# Power.net
KiCad netlist of a schematic drawn in Altium Designer
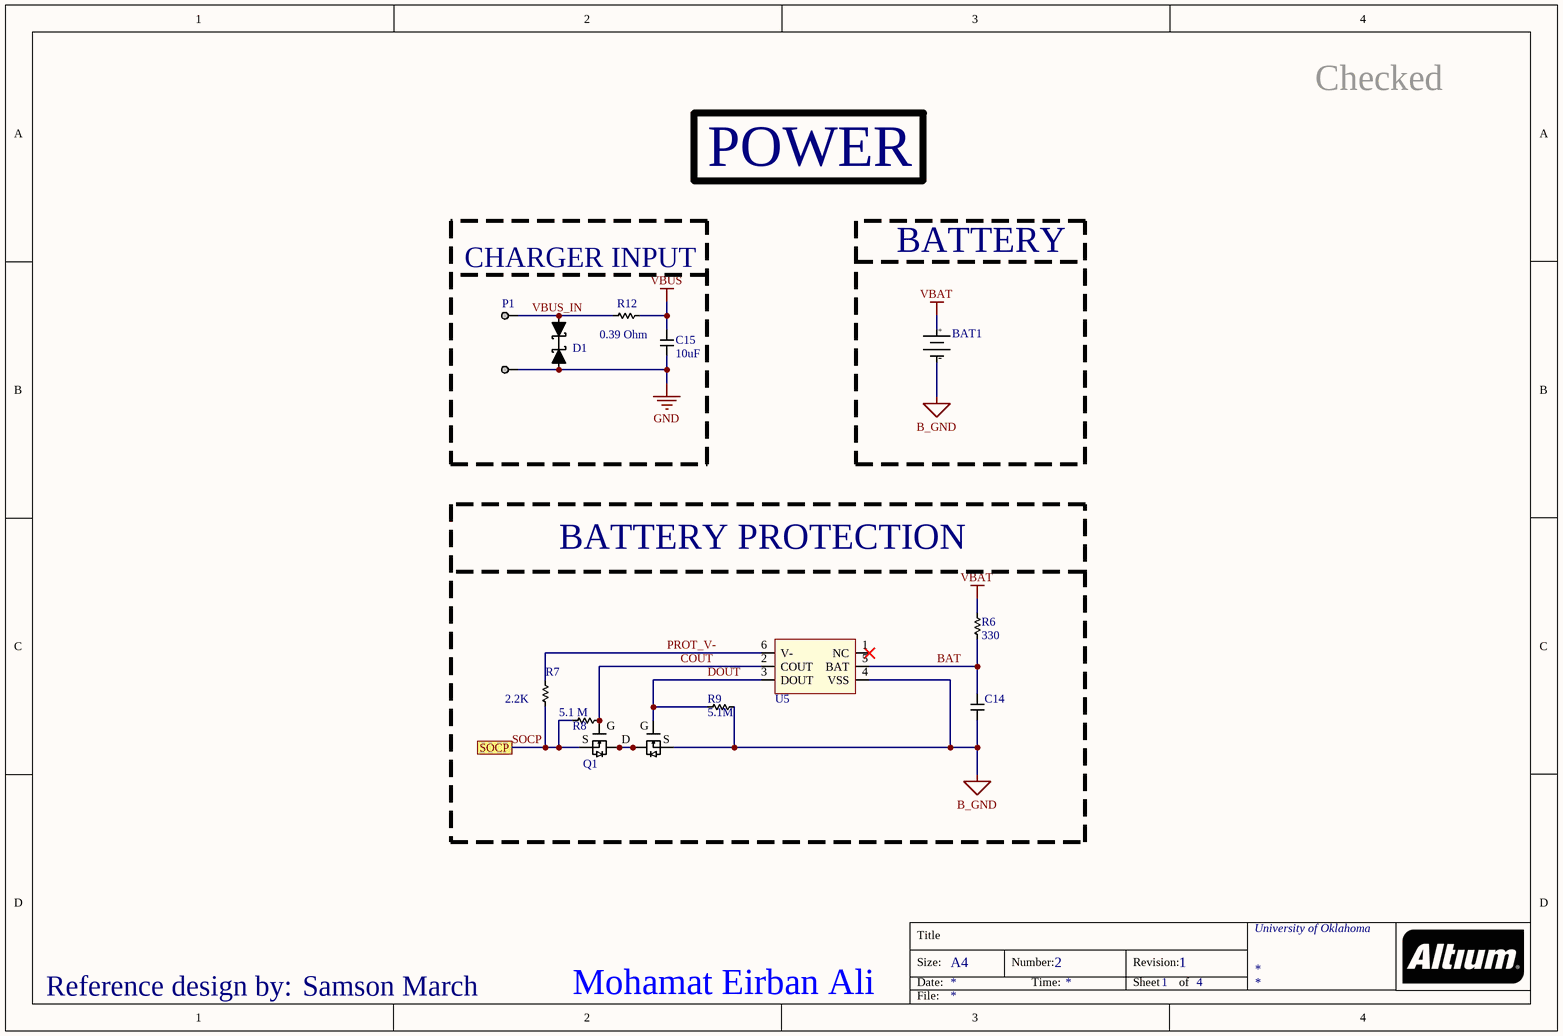
[diagram p0: Power.SchDoc]

(export (version "E")
  (design (tool "Eeschema 10.0.6"))
  (components
    (comp (ref "BAT1")
      (value "~")
      (footprint "RJD2430C1ST1")
      (description "Coin, 24.5mm 3.7V Lithium-Ion Battery Rechargeable (Secondary) 110mAh")
      (libsource (lib "smarchWatch_V5") (part "RJD2430C1ST1"))
    )
    (comp (ref "C14")
      (value "~")
      (footprint "CAP_0603_HIGH")
      (description "0603 Capacitor")
      (fields (field (name "TOLERANCE") "10%") (field (name "VOLTAGE") "50V"))
      (libsource (lib "smarchWatch_V5") (part "Capacitor_0603"))
    )
    (comp (ref "C15")
      (value "10uF")
      (footprint "CAP_0603_HIGH")
      (description "0603 Capacitor")
      (libsource (lib "smarchWatch_V5") (part "Capacitor_0603_1"))
    )
    (comp (ref "D1")
      (value "~")
      (footprint "ESD9B5.0ST5G")
      (description "TVS DIODE 5V SOD923")
      (libsource (lib "smarchWatch_V5") (part "ESD9B5.0ST5G"))
    )
    (comp (ref "P1")
      (value "~")
      (footprint "800-10-002-30-507101")
      (description "2 Position Spring Mating Target Connector Surface Mount")
      (libsource (lib "smarchWatch_V5") (part "800-10-002-30-507101"))
    )
    (comp (ref "Q1")
      (value "~")
      (footprint "ECH8693R-TL-W")
      (description "Mosfet Array 2 N-Channel (Dual) Common Drain 24V 14A 1.4W Surface Mount SOT-28FL/ECH8")
      (libsource (lib "smarchWatch_V5") (part "ECH8693R-TL-W"))
    )
    (comp (ref "R6")
      (value "330")
      (footprint "RES_0603_HIGH")
      (description "0603 Resistor")
      (libsource (lib "smarchWatch_V5") (part "Resistor_0603_2"))
    )
    (comp (ref "R7")
      (value "2.2K")
      (footprint "RES_0603_HIGH")
      (description "0603 Resistor")
      (libsource (lib "smarchWatch_V5") (part "Resistor_0603_1"))
    )
    (comp (ref "R8")
      (value "5.1 M")
      (footprint "RES_0603_HIGH")
      (description "0603 Resistor")
      (fields (field (name "TOLERANCE") "5%"))
      (libsource (lib "smarchWatch_V5") (part "Resistor_0603"))
    )
    (comp (ref "R9")
      (value "5.1M")
      (footprint "RES_0603_HIGH")
      (description "0603 Resistor")
      (fields (field (name "TOLERANCE") "5%"))
      (libsource (lib "smLib") (part "Resistor_0603"))
    )
    (comp (ref "R12")
      (value "0.39 Ohm")
      (footprint "RES_0805_HIGH")
      (description "0805 Resistor")
      (libsource (lib "smarchWatch_V5") (part "Resistor_0805"))
    )
    (comp (ref "U5")
      (value "~")
      (footprint "BQ29700DSER")
      (description "Battery Battery Protection IC Lithium-Ion/Polymer 6-WSON (1.5x1.5)")
      (libsource (lib "smarchWatch_V5") (part "BQ29700DSER"))
    )
  )
  (nets
    (net (code "1") (name "/BAT") (class "Default")
      (node (ref "C14") (pin "1") (pinfunction "1_1") (pintype "passive"))
      (node (ref "R6") (pin "2") (pinfunction "2_2") (pintype "passive"))
      (node (ref "U5") (pin "5") (pinfunction "BAT_5") (pintype "passive"))
    )
    (net (code "2") (name "/COUT") (class "Default")
      (node (ref "Q1") (pin "2") (pinfunction "G1_2") (pintype "passive"))
      (node (ref "R8") (pin "1") (pinfunction "1_1") (pintype "passive"))
      (node (ref "U5") (pin "2") (pinfunction "COUT_2") (pintype "passive"))
    )
    (net (code "3") (name "/DOUT") (class "Default")
      (node (ref "Q1") (pin "4") (pinfunction "G2_4") (pintype "passive"))
      (node (ref "R9") (pin "2") (pinfunction "2_2") (pintype "passive"))
      (node (ref "U5") (pin "3") (pinfunction "DOUT_3") (pintype "passive"))
    )
    (net (code "4") (name "/PROT_V-") (class "Default")
      (node (ref "R7") (pin "1") (pinfunction "1_1") (pintype "passive"))
      (node (ref "U5") (pin "6") (pinfunction "V-_6") (pintype "passive"))
    )
    (net (code "5") (name "/SOCP") (class "Default")
      (node (ref "Q1") (pin "1") (pinfunction "S1_1") (pintype "passive"))
      (node (ref "R7") (pin "2") (pinfunction "2_2") (pintype "passive"))
      (node (ref "R8") (pin "2") (pinfunction "2_2") (pintype "passive"))
    )
    (net (code "6") (name "/VBUS_IN") (class "Default")
      (node (ref "D1") (pin "2") (pinfunction "2_2") (pintype "passive"))
      (node (ref "P1") (pin "1") (pinfunction "1_1") (pintype "passive"))
      (node (ref "R12") (pin "1") (pinfunction "1_1") (pintype "passive"))
    )
    (net (code "7") (name "B_GND") (class "Default")
      (node (ref "BAT1") (pin "2") (pinfunction "-_2") (pintype "passive"))
      (node (ref "C14") (pin "2") (pinfunction "2_2") (pintype "passive"))
      (node (ref "Q1") (pin "3") (pinfunction "S2_3") (pintype "passive"))
      (node (ref "R9") (pin "1") (pinfunction "1_1") (pintype "passive"))
      (node (ref "U5") (pin "4") (pinfunction "VSS_4") (pintype "passive"))
    )
    (net (code "8") (name "GND") (class "Default")
      (node (ref "C15") (pin "2") (pinfunction "2_2") (pintype "passive"))
      (node (ref "D1") (pin "1") (pinfunction "1_1") (pintype "passive"))
      (node (ref "P1") (pin "2") (pinfunction "2_2") (pintype "passive"))
    )
    (net (code "9") (name "Net-(Q1-D-Pad5)") (class "Default")
      (node (ref "Q1") (pin "5") (pinfunction "D_5") (pintype "passive"))
      (node (ref "Q1") (pin "6") (pinfunction "D_6") (pintype "passive"))
      (node (ref "Q1") (pin "7") (pinfunction "D_7") (pintype "passive"))
      (node (ref "Q1") (pin "8") (pinfunction "D_8") (pintype "passive"))
    )
    (net (code "10") (name "VBAT") (class "Default")
      (node (ref "BAT1") (pin "1") (pinfunction "+_1") (pintype "passive"))
      (node (ref "R6") (pin "1") (pinfunction "1_1") (pintype "passive"))
    )
    (net (code "11") (name "VBUS") (class "Default")
      (node (ref "C15") (pin "1") (pinfunction "1_1") (pintype "passive"))
      (node (ref "R12") (pin "2") (pinfunction "2_2") (pintype "passive"))
    )
    (net (code "12") (name "unconnected-(U5-NC-Pad1)") (class "Default")
      (node (ref "U5") (pin "1") (pinfunction "NC_1") (pintype "passive+no_connect"))
    )
  )
)
